# ADC_and_IMU.net
KiCad netlist of a schematic drawn in Altium Designer
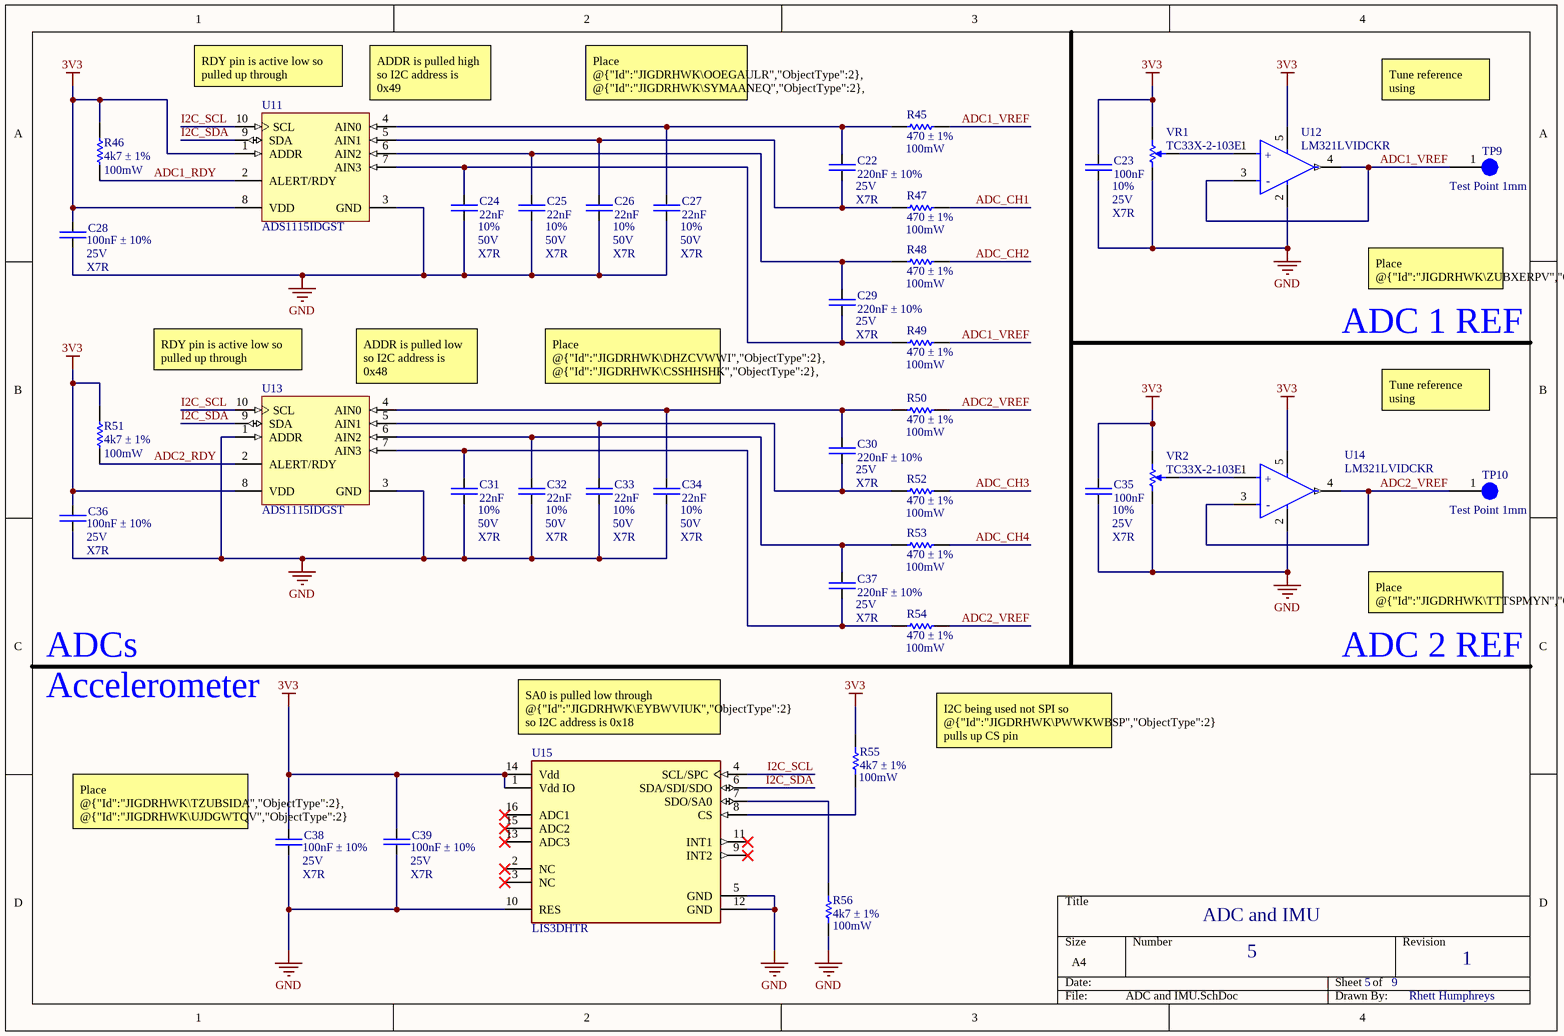
[diagram p0: ADC and IMU.SchDoc]

(export (version "E")
  (design (tool "Eeschema 10.0.6"))
  (components
    (comp (ref "C22")
      (value "220nF ± 10%")
      (footprint "CAP-0603")
      (description "Capacitor chip unpolarized. 0603")
      (libsource (lib "Master") (part "CAP-0603"))
    )
    (comp (ref "C23")
      (value "100nF")
      (footprint "CAP-0603")
      (description "Capacitor chip unpolarized. 0603")
      (libsource (lib "Master") (part "CAP-0603"))
    )
    (comp (ref "C24")
      (value "22nF")
      (footprint "CAP-0603")
      (description "Capacitor chip unpolarized. 0603")
      (libsource (lib "Master") (part "CAP-0603"))
    )
    (comp (ref "C25")
      (value "22nF")
      (footprint "CAP-0603")
      (description "Capacitor chip unpolarized. 0603")
      (libsource (lib "Master") (part "CAP-0603"))
    )
    (comp (ref "C26")
      (value "22nF")
      (footprint "CAP-0603")
      (description "Capacitor chip unpolarized. 0603")
      (libsource (lib "Master") (part "CAP-0603"))
    )
    (comp (ref "C27")
      (value "22nF")
      (footprint "CAP-0603")
      (description "Capacitor chip unpolarized. 0603")
      (libsource (lib "Master") (part "CAP-0603"))
    )
    (comp (ref "C28")
      (value "100nF ± 10%")
      (footprint "CAP-0603")
      (description "Capacitor chip unpolarized. 0603")
      (libsource (lib "Master") (part "CAP-0603"))
    )
    (comp (ref "C29")
      (value "220nF ± 10%")
      (footprint "CAP-0603")
      (description "Capacitor chip unpolarized. 0603")
      (libsource (lib "Master") (part "CAP-0603"))
    )
    (comp (ref "C30")
      (value "220nF ± 10%")
      (footprint "CAP-0603")
      (description "Capacitor chip unpolarized. 0603")
      (libsource (lib "Master") (part "CAP-0603"))
    )
    (comp (ref "C31")
      (value "22nF")
      (footprint "CAP-0603")
      (description "Capacitor chip unpolarized. 0603")
      (libsource (lib "Master") (part "CAP-0603"))
    )
    (comp (ref "C32")
      (value "22nF")
      (footprint "CAP-0603")
      (description "Capacitor chip unpolarized. 0603")
      (libsource (lib "Master") (part "CAP-0603"))
    )
    (comp (ref "C33")
      (value "22nF")
      (footprint "CAP-0603")
      (description "Capacitor chip unpolarized. 0603")
      (libsource (lib "Master") (part "CAP-0603"))
    )
    (comp (ref "C34")
      (value "22nF")
      (footprint "CAP-0603")
      (description "Capacitor chip unpolarized. 0603")
      (libsource (lib "Master") (part "CAP-0603"))
    )
    (comp (ref "C35")
      (value "100nF")
      (footprint "CAP-0603")
      (description "Capacitor chip unpolarized. 0603")
      (libsource (lib "Master") (part "CAP-0603"))
    )
    (comp (ref "C36")
      (value "100nF ± 10%")
      (footprint "CAP-0603")
      (description "Capacitor chip unpolarized. 0603")
      (libsource (lib "Master") (part "CAP-0603"))
    )
    (comp (ref "C37")
      (value "220nF ± 10%")
      (footprint "CAP-0603")
      (description "Capacitor chip unpolarized. 0603")
      (libsource (lib "Master") (part "CAP-0603"))
    )
    (comp (ref "C38")
      (value "100nF ± 10%")
      (footprint "CAP-0603")
      (description "Capacitor chip unpolarized. 0603")
      (libsource (lib "Master") (part "CAP-0603"))
    )
    (comp (ref "C39")
      (value "100nF ± 10%")
      (footprint "CAP-0603")
      (description "Capacitor chip unpolarized. 0603")
      (libsource (lib "Master") (part "CAP-0603"))
    )
    (comp (ref "R45")
      (value "470 ± 1%")
      (footprint "RES-0603")
      (description "Resistor chip. 0603")
      (libsource (lib "Master") (part "RES-0603"))
    )
    (comp (ref "R46")
      (value "4k7 ± 1%")
      (footprint "RES-0603")
      (description "Resistor chip. 0603")
      (libsource (lib "Master") (part "RES-0603"))
    )
    (comp (ref "R47")
      (value "470 ± 1%")
      (footprint "RES-0603")
      (description "Resistor chip. 0603")
      (libsource (lib "Master") (part "RES-0603"))
    )
    (comp (ref "R48")
      (value "470 ± 1%")
      (footprint "RES-0603")
      (description "Resistor chip. 0603")
      (libsource (lib "Master") (part "RES-0603"))
    )
    (comp (ref "R49")
      (value "470 ± 1%")
      (footprint "RES-0603")
      (description "Resistor chip. 0603")
      (libsource (lib "Master") (part "RES-0603"))
    )
    (comp (ref "R50")
      (value "470 ± 1%")
      (footprint "RES-0603")
      (description "Resistor chip. 0603")
      (libsource (lib "Master") (part "RES-0603"))
    )
    (comp (ref "R51")
      (value "4k7 ± 1%")
      (footprint "RES-0603")
      (description "Resistor chip. 0603")
      (libsource (lib "Master") (part "RES-0603"))
    )
    (comp (ref "R52")
      (value "470 ± 1%")
      (footprint "RES-0603")
      (description "Resistor chip. 0603")
      (libsource (lib "Master") (part "RES-0603"))
    )
    (comp (ref "R53")
      (value "470 ± 1%")
      (footprint "RES-0603")
      (description "Resistor chip. 0603")
      (libsource (lib "Master") (part "RES-0603"))
    )
    (comp (ref "R54")
      (value "470 ± 1%")
      (footprint "RES-0603")
      (description "Resistor chip. 0603")
      (libsource (lib "Master") (part "RES-0603"))
    )
    (comp (ref "R55")
      (value "4k7 ± 1%")
      (footprint "RESC1609X50X30NL8T20")
      (description "Chip Resistor, 10 KOhm, +/- 1%, 100 mW, -55 to 155 degC, 0603 (1608 Metric), RoHS, Tape and Reel")
      (fields (field (name "MANUFACTURER") "Vishay Semiconductor"))
      (libsource (lib "Altium Content Vault") (part "RES-2"))
    )
    (comp (ref "R56")
      (value "4k7 ± 1%")
      (footprint "RESC1609X50X30NL8T20")
      (description "Chip Resistor, 10 KOhm, +/- 1%, 100 mW, -55 to 155 degC, 0603 (1608 Metric), RoHS, Tape and Reel")
      (fields (field (name "MANUFACTURER") "Vishay Semiconductor"))
      (libsource (lib "Altium Content Vault") (part "RES-2"))
    )
    (comp (ref "TP9")
      (value "Test Point 1mm")
      (footprint "Test Point 1mm")
      (libsource (lib "Master") (part "Test Point 1mm"))
    )
    (comp (ref "TP10")
      (value "Test Point 1mm")
      (footprint "Test Point 1mm")
      (libsource (lib "Master") (part "Test Point 1mm"))
    )
    (comp (ref "U11")
      (value "ADS1115IDGST")
      (footprint "TI-DGS10_M")
      (fields (field (name "MANUFACTURER") "Texas Instruments"))
      (libsource (lib "Altium Content Vault") (part "TI-ADS1015_1115-10"))
    )
    (comp (ref "U12")
      (value "LM321LVIDCKR")
      (footprint "FP-DCK0005A-IPC_B")
      (description "IC OPAMP GP 1 CIRCUIT SC70-5")
      (libsource (lib "Altium Content Vault") (part "471d8b929410cd356ad4b122f572ce5"))
    )
    (comp (ref "U13")
      (value "ADS1115IDGST")
      (footprint "TI-DGS10_M")
      (fields (field (name "MANUFACTURER") "Texas Instruments"))
      (libsource (lib "Altium Content Vault") (part "TI-ADS1015_1115-10"))
    )
    (comp (ref "U14")
      (value "LM321LVIDCKR")
      (footprint "FP-DCK0005A-IPC_B")
      (description "IC OPAMP GP 1 CIRCUIT SC70-5")
      (libsource (lib "Altium Content Vault") (part "471d8b929410cd356ad4b122f572ce5"))
    )
    (comp (ref "U15")
      (value "LIS3DHTR")
      (footprint "FP-LGA-16-7983231-MFG")
      (description "ACCEL 2-16G I2C/SPI 16LGA")
      (libsource (lib "Altium Content Vault") (part "1e4772b22d749da4b53766bc623c8dd"))
    )
    (comp (ref "VR1")
      (value "TC33X-2-103E")
      (footprint "BOUR-TC33X-2_V")
      (description "Trimming Potentiometer, 10000 Ohm, -40 to 100 degC, 3-Pin SMD, RoHS, Tape and Reel")
      (fields (field (name "TOLERANCE") "25%") (field (name "MANUFACTURER") "Bourns"))
      (libsource (lib "Altium Content Vault") (part "RES-ADJ-3_A"))
    )
    (comp (ref "VR2")
      (value "TC33X-2-103E")
      (footprint "BOUR-TC33X-2_V")
      (description "Trimming Potentiometer, 10000 Ohm, -40 to 100 degC, 3-Pin SMD, RoHS, Tape and Reel")
      (fields (field (name "TOLERANCE") "25%") (field (name "MANUFACTURER") "Bourns"))
      (libsource (lib "Altium Content Vault") (part "RES-ADJ-3_A"))
    )
  )
  (nets
    (net (code "1") (name "/ADC1_RDY") (class "Default")
      (node (ref "R46") (pin "1") (pintype "passive"))
      (node (ref "U11") (pin "2") (pinfunction "ALERT/RDY_2") (pintype "open_collector"))
    )
    (net (code "2") (name "/ADC1_VREF") (class "Default")
      (node (ref "R45") (pin "1") (pintype "passive"))
      (node (ref "R49") (pin "1") (pintype "passive"))
      (node (ref "TP9") (pin "1") (pintype "passive"))
      (node (ref "U12") (pin "3") (pinfunction "IN-_3") (pintype "tri_state"))
      (node (ref "U12") (pin "4") (pinfunction "OUT_4") (pintype "output"))
    )
    (net (code "3") (name "/ADC2_RDY") (class "Default")
      (node (ref "R51") (pin "1") (pintype "passive"))
      (node (ref "U13") (pin "2") (pinfunction "ALERT/RDY_2") (pintype "open_collector"))
    )
    (net (code "4") (name "/ADC2_VREF") (class "Default")
      (node (ref "R50") (pin "1") (pintype "passive"))
      (node (ref "R54") (pin "1") (pintype "passive"))
      (node (ref "TP10") (pin "1") (pintype "passive"))
      (node (ref "U14") (pin "3") (pinfunction "IN-_3") (pintype "tri_state"))
      (node (ref "U14") (pin "4") (pinfunction "OUT_4") (pintype "output"))
    )
    (net (code "5") (name "/ADC_CH1") (class "Default") (node (ref "R47") (pin "1") (pintype "passive")))
    (net (code "6") (name "/ADC_CH2") (class "Default") (node (ref "R48") (pin "1") (pintype "passive")))
    (net (code "7") (name "/ADC_CH3") (class "Default") (node (ref "R52") (pin "1") (pintype "passive")))
    (net (code "8") (name "/ADC_CH4") (class "Default") (node (ref "R53") (pin "1") (pintype "passive")))
    (net (code "9") (name "/I2C_SCL") (class "Default")
      (node (ref "U11") (pin "10") (pinfunction "SCL_10") (pintype "input"))
      (node (ref "U13") (pin "10") (pinfunction "SCL_10") (pintype "input"))
      (node (ref "U15") (pin "4") (pinfunction "SCL/SPC_4") (pintype "input"))
    )
    (net (code "10") (name "/I2C_SDA") (class "Default")
      (node (ref "U11") (pin "9") (pinfunction "SDA_9") (pintype "bidirectional"))
      (node (ref "U13") (pin "9") (pinfunction "SDA_9") (pintype "bidirectional"))
      (node (ref "U15") (pin "6") (pinfunction "SDA/SDI/SDO_6") (pintype "bidirectional"))
    )
    (net (code "11") (name "3V3") (class "Default")
      (node (ref "C23") (pin "2") (pintype "passive"))
      (node (ref "C28") (pin "2") (pintype "passive"))
      (node (ref "C35") (pin "2") (pintype "passive"))
      (node (ref "C36") (pin "2") (pintype "passive"))
      (node (ref "C38") (pin "2") (pintype "passive"))
      (node (ref "C39") (pin "2") (pintype "passive"))
      (node (ref "R46") (pin "2") (pintype "passive"))
      (node (ref "R51") (pin "2") (pintype "passive"))
      (node (ref "R55") (pin "2") (pinfunction "2_2") (pintype "passive"))
      (node (ref "U11") (pin "1") (pinfunction "ADDR_1") (pintype "input"))
      (node (ref "U11") (pin "8") (pinfunction "VDD_8") (pintype "power_in"))
      (node (ref "U12") (pin "5") (pinfunction "V+_5") (pintype "power_in"))
      (node (ref "U13") (pin "8") (pinfunction "VDD_8") (pintype "power_in"))
      (node (ref "U14") (pin "5") (pinfunction "V+_5") (pintype "power_in"))
      (node (ref "U15") (pin "1") (pinfunction "Vdd_IO_1") (pintype "power_in"))
      (node (ref "U15") (pin "14") (pinfunction "Vdd_14") (pintype "power_in"))
      (node (ref "VR1") (pin "3") (pinfunction "3_3") (pintype "passive"))
      (node (ref "VR2") (pin "3") (pinfunction "3_3") (pintype "passive"))
    )
    (net (code "12") (name "GND") (class "Default")
      (node (ref "C23") (pin "1") (pintype "passive"))
      (node (ref "C24") (pin "1") (pintype "passive"))
      (node (ref "C25") (pin "1") (pintype "passive"))
      (node (ref "C26") (pin "1") (pintype "passive"))
      (node (ref "C27") (pin "1") (pintype "passive"))
      (node (ref "C28") (pin "1") (pintype "passive"))
      (node (ref "C31") (pin "1") (pintype "passive"))
      (node (ref "C32") (pin "1") (pintype "passive"))
      (node (ref "C33") (pin "1") (pintype "passive"))
      (node (ref "C34") (pin "1") (pintype "passive"))
      (node (ref "C35") (pin "1") (pintype "passive"))
      (node (ref "C36") (pin "1") (pintype "passive"))
      (node (ref "C38") (pin "1") (pintype "passive"))
      (node (ref "C39") (pin "1") (pintype "passive"))
      (node (ref "R56") (pin "1") (pinfunction "1_1") (pintype "passive"))
      (node (ref "U11") (pin "3") (pinfunction "GND_3") (pintype "power_in"))
      (node (ref "U12") (pin "2") (pinfunction "V-_2") (pintype "power_in"))
      (node (ref "U13") (pin "1") (pinfunction "ADDR_1") (pintype "input"))
      (node (ref "U13") (pin "3") (pinfunction "GND_3") (pintype "power_in"))
      (node (ref "U14") (pin "2") (pinfunction "V-_2") (pintype "power_in"))
      (node (ref "U15") (pin "10") (pinfunction "RES_10") (pintype "passive"))
      (node (ref "U15") (pin "12") (pinfunction "GND_12") (pintype "power_in"))
      (node (ref "U15") (pin "5") (pinfunction "GND_5") (pintype "power_in"))
      (node (ref "VR1") (pin "1") (pinfunction "1_1") (pintype "passive"))
      (node (ref "VR2") (pin "1") (pinfunction "1_1") (pintype "passive"))
    )
    (net (code "13") (name "Net-(U11-AIN0)") (class "Default")
      (node (ref "C22") (pin "2") (pintype "passive"))
      (node (ref "C27") (pin "2") (pintype "passive"))
      (node (ref "R45") (pin "2") (pintype "passive"))
      (node (ref "U11") (pin "4") (pinfunction "AIN0_4") (pintype "input"))
    )
    (net (code "14") (name "Net-(U11-AIN1)") (class "Default")
      (node (ref "C22") (pin "1") (pintype "passive"))
      (node (ref "C26") (pin "2") (pintype "passive"))
      (node (ref "R47") (pin "2") (pintype "passive"))
      (node (ref "U11") (pin "5") (pinfunction "AIN1_5") (pintype "input"))
    )
    (net (code "15") (name "Net-(U11-AIN2)") (class "Default")
      (node (ref "C25") (pin "2") (pintype "passive"))
      (node (ref "C29") (pin "2") (pintype "passive"))
      (node (ref "R48") (pin "2") (pintype "passive"))
      (node (ref "U11") (pin "6") (pinfunction "AIN2_6") (pintype "input"))
    )
    (net (code "16") (name "Net-(U11-AIN3)") (class "Default")
      (node (ref "C24") (pin "2") (pintype "passive"))
      (node (ref "C29") (pin "1") (pintype "passive"))
      (node (ref "R49") (pin "2") (pintype "passive"))
      (node (ref "U11") (pin "7") (pinfunction "AIN3_7") (pintype "input"))
    )
    (net (code "17") (name "Net-(U12-IN+)") (class "Default")
      (node (ref "U12") (pin "1") (pinfunction "IN+_1") (pintype "tri_state"))
      (node (ref "VR1") (pin "2") (pinfunction "2_2") (pintype "passive"))
    )
    (net (code "18") (name "Net-(U13-AIN0)") (class "Default")
      (node (ref "C30") (pin "2") (pintype "passive"))
      (node (ref "C34") (pin "2") (pintype "passive"))
      (node (ref "R50") (pin "2") (pintype "passive"))
      (node (ref "U13") (pin "4") (pinfunction "AIN0_4") (pintype "input"))
    )
    (net (code "19") (name "Net-(U13-AIN1)") (class "Default")
      (node (ref "C30") (pin "1") (pintype "passive"))
      (node (ref "C33") (pin "2") (pintype "passive"))
      (node (ref "R52") (pin "2") (pintype "passive"))
      (node (ref "U13") (pin "5") (pinfunction "AIN1_5") (pintype "input"))
    )
    (net (code "20") (name "Net-(U13-AIN2)") (class "Default")
      (node (ref "C32") (pin "2") (pintype "passive"))
      (node (ref "C37") (pin "2") (pintype "passive"))
      (node (ref "R53") (pin "2") (pintype "passive"))
      (node (ref "U13") (pin "6") (pinfunction "AIN2_6") (pintype "input"))
    )
    (net (code "21") (name "Net-(U13-AIN3)") (class "Default")
      (node (ref "C31") (pin "2") (pintype "passive"))
      (node (ref "C37") (pin "1") (pintype "passive"))
      (node (ref "R54") (pin "2") (pintype "passive"))
      (node (ref "U13") (pin "7") (pinfunction "AIN3_7") (pintype "input"))
    )
    (net (code "22") (name "Net-(U14-IN+)") (class "Default")
      (node (ref "U14") (pin "1") (pinfunction "IN+_1") (pintype "tri_state"))
      (node (ref "VR2") (pin "2") (pinfunction "2_2") (pintype "passive"))
    )
    (net (code "23") (name "Net-(U15-CS)") (class "Default")
      (node (ref "R55") (pin "1") (pinfunction "1_1") (pintype "passive"))
      (node (ref "U15") (pin "8") (pinfunction "CS_8") (pintype "input"))
    )
    (net (code "24") (name "Net-(U15-SDO{slash}SA0)") (class "Default")
      (node (ref "R56") (pin "2") (pinfunction "2_2") (pintype "passive"))
      (node (ref "U15") (pin "7") (pinfunction "SDO/SA0_7") (pintype "bidirectional"))
    )
    (net (code "25") (name "unconnected-(U15-ADC1-Pad16)") (class "Default")
      (node (ref "U15") (pin "16") (pinfunction "ADC1_16") (pintype "passive+no_connect"))
    )
    (net (code "26") (name "unconnected-(U15-ADC2-Pad15)") (class "Default")
      (node (ref "U15") (pin "15") (pinfunction "ADC2_15") (pintype "passive+no_connect"))
    )
    (net (code "27") (name "unconnected-(U15-ADC3-Pad13)") (class "Default")
      (node (ref "U15") (pin "13") (pinfunction "ADC3_13") (pintype "passive+no_connect"))
    )
    (net (code "28") (name "unconnected-(U15-INT1-Pad11)") (class "Default")
      (node (ref "U15") (pin "11") (pinfunction "INT1_11") (pintype "output+no_connect"))
    )
    (net (code "29") (name "unconnected-(U15-INT2-Pad9)") (class "Default")
      (node (ref "U15") (pin "9") (pinfunction "INT2_9") (pintype "output+no_connect"))
    )
    (net (code "30") (name "unconnected-(U15-NC-Pad2)") (class "Default")
      (node (ref "U15") (pin "2") (pinfunction "NC_2") (pintype "passive+no_connect"))
    )
    (net (code "31") (name "unconnected-(U15-NC-Pad3)") (class "Default")
      (node (ref "U15") (pin "3") (pinfunction "NC_3") (pintype "passive+no_connect"))
    )
  )
)
